# Adafruit_SEN5x_Adapter_Breakout.net
KiCad netlist of a schematic drawn in EAGLE
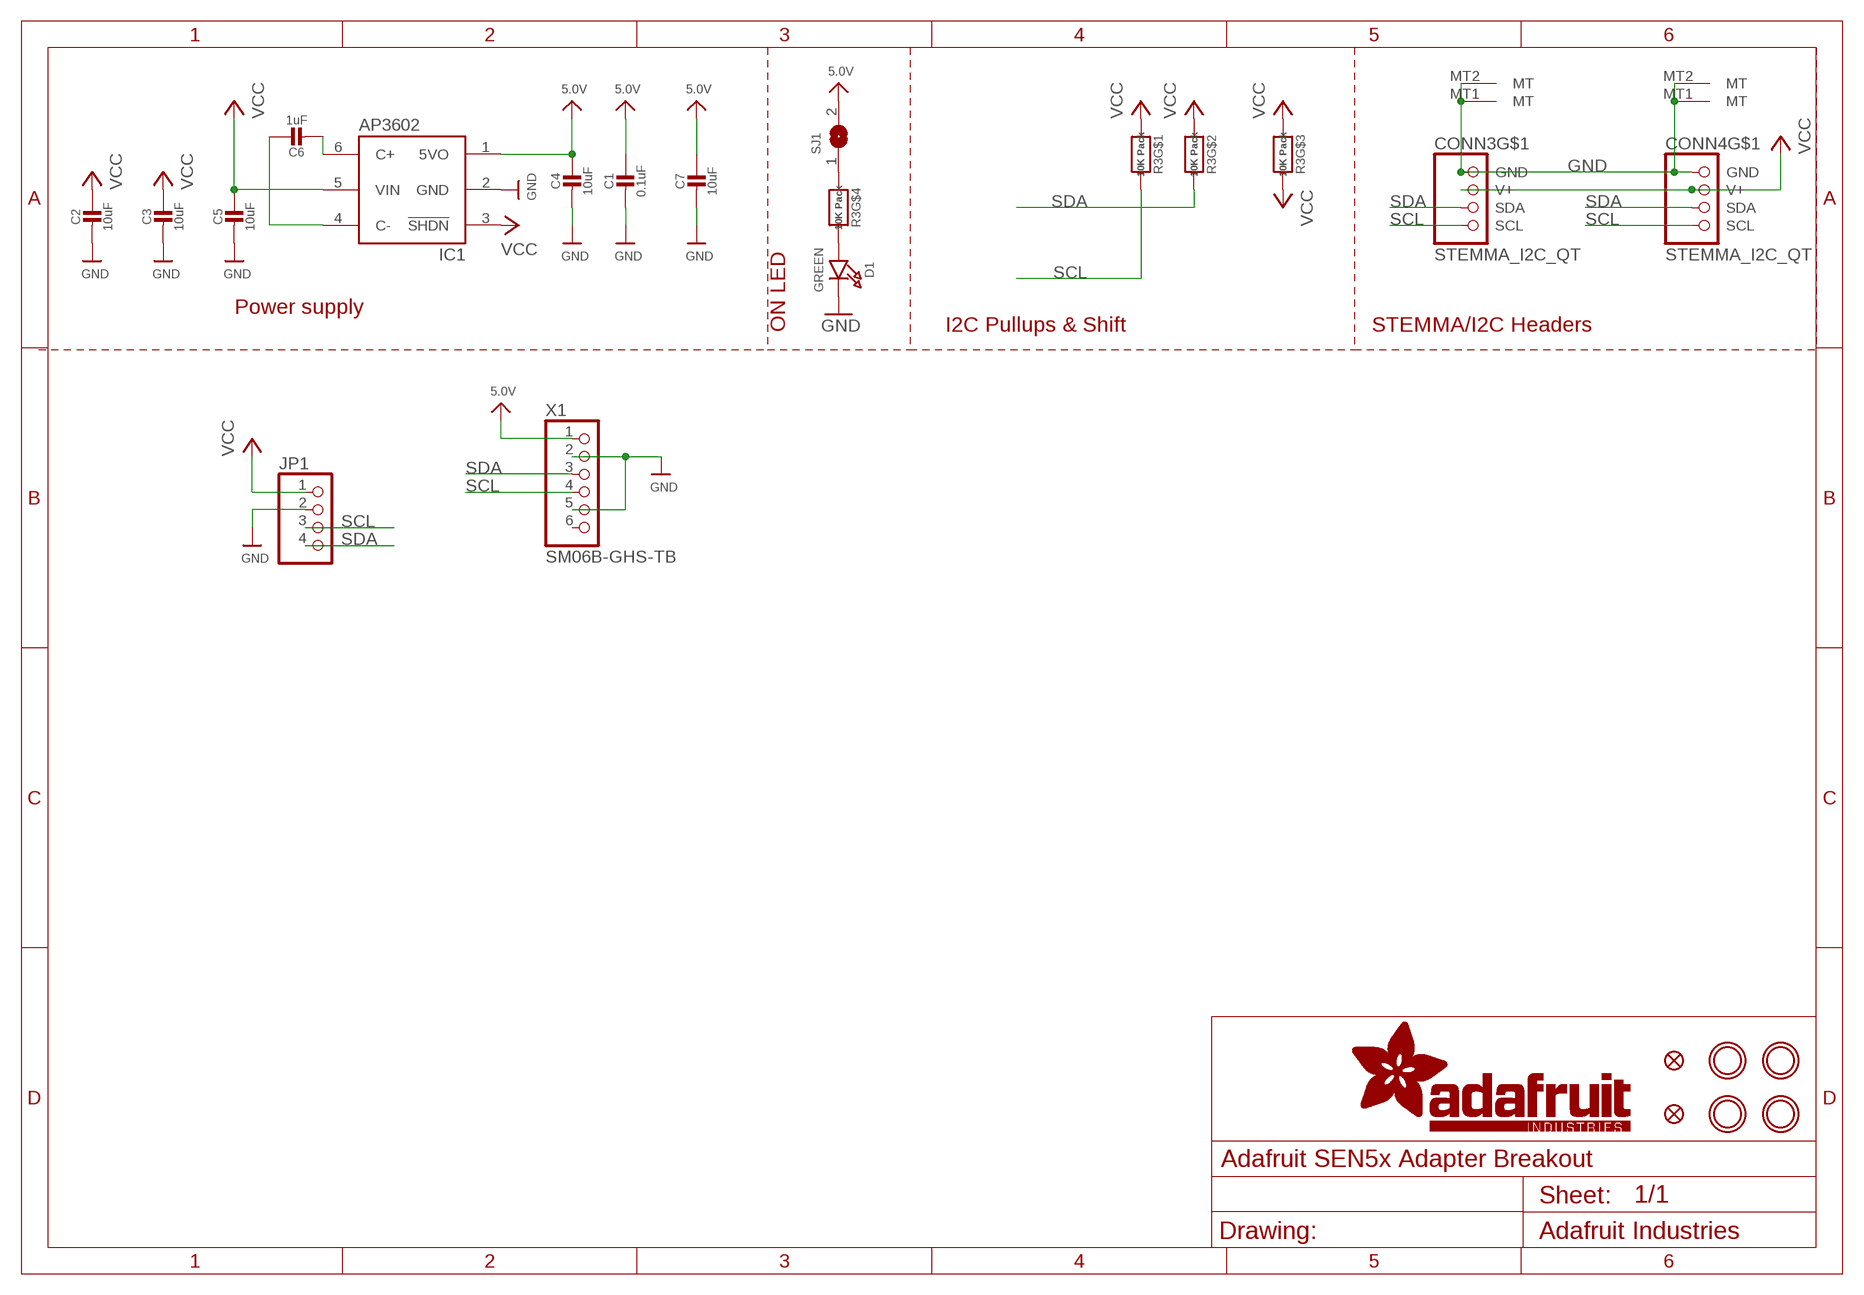
[diagram p0: schematic, sheet 1]

(export (version "E")
  (design (tool "Eeschema 10.0.6"))
  (components
    (comp (ref "C1")
      (value "0.1uF")
      (footprint "eagle-import:0603-NO")
      (libsource (lib "eagle-import") (part "CAP_CERAMIC0603_NO"))
    )
    (comp (ref "C2")
      (value "10uF")
      (footprint "eagle-import:0805-NO")
      (libsource (lib "eagle-import") (part "CAP_CERAMIC0805-NOOUTLINE"))
    )
    (comp (ref "C3")
      (value "10uF")
      (footprint "eagle-import:0805-NO")
      (libsource (lib "eagle-import") (part "CAP_CERAMIC0805-NOOUTLINE"))
    )
    (comp (ref "C4")
      (value "10uF")
      (footprint "eagle-import:0805-NO")
      (libsource (lib "eagle-import") (part "CAP_CERAMIC0805-NOOUTLINE"))
    )
    (comp (ref "C5")
      (value "10uF")
      (footprint "eagle-import:0805-NO")
      (libsource (lib "eagle-import") (part "CAP_CERAMIC0805-NOOUTLINE"))
    )
    (comp (ref "C6")
      (value "1uF")
      (footprint "eagle-import:0805-NO")
      (libsource (lib "eagle-import") (part "CAP_CERAMIC0805-NOOUTLINE"))
    )
    (comp (ref "C7")
      (value "10uF")
      (footprint "eagle-import:0805-NO")
      (libsource (lib "eagle-import") (part "CAP_CERAMIC0805-NOOUTLINE"))
    )
    (comp (ref "CONN3")
      (value "STEMMA_I2C_QT")
      (footprint "eagle-import:JST_SH4")
      (libsource (lib "eagle-import") (part "STEMMA_I2C_QT"))
    )
    (comp (ref "CONN4")
      (value "STEMMA_I2C_QT")
      (footprint "eagle-import:JST_SH4")
      (libsource (lib "eagle-import") (part "STEMMA_I2C_QT"))
    )
    (comp (ref "D1")
      (value "GREEN")
      (footprint "eagle-import:CHIPLED_0603_NOOUTLINE")
      (libsource (lib "eagle-import") (part "LED0603_NOOUTLINE"))
    )
    (comp (ref "FID3")
      (value "FIDUCIAL_1MM")
      (footprint "eagle-import:FIDUCIAL_1MM")
      (libsource (lib "eagle-import") (part "FIDUCIAL_1MM"))
    )
    (comp (ref "FID4")
      (value "FIDUCIAL_1MM")
      (footprint "eagle-import:FIDUCIAL_1MM")
      (libsource (lib "eagle-import") (part "FIDUCIAL_1MM"))
    )
    (comp (ref "IC1")
      (value "AP3602/RT9361")
      (footprint "eagle-import:SOT23-6")
      (libsource (lib "eagle-import") (part "AP3602"))
    )
    (comp (ref "JP1")
      (value "HEADER-1X4ROUND")
      (footprint "eagle-import:1X04_ROUND")
      (libsource (lib "eagle-import") (part "HEADER-1X4ROUND"))
    )
    (comp (ref "R3")
      (value "10K Pack")
      (footprint "eagle-import:RESPACK_4X0603")
      (libsource (lib "eagle-import") (part "RESISTOR_4PACK"))
    )
    (comp (ref "SJ1")
      (value "SOLDERJUMPERCLOSED")
      (footprint "eagle-import:SOLDERJUMPER_CLOSEDWIRE")
      (libsource (lib "eagle-import") (part "SOLDERJUMPERCLOSED"))
    )
    (comp (ref "U$1")
      (value "MOUNTINGHOLE2.5")
      (footprint "eagle-import:MOUNTINGHOLE_2.5_PLATED")
      (libsource (lib "eagle-import") (part "MOUNTINGHOLE2.5"))
    )
    (comp (ref "U$17")
      (value "MOUNTINGHOLE2.5")
      (footprint "eagle-import:MOUNTINGHOLE_2.5_PLATED")
      (libsource (lib "eagle-import") (part "MOUNTINGHOLE2.5"))
    )
    (comp (ref "U$19")
      (value "MOUNTINGHOLE2.5")
      (footprint "eagle-import:MOUNTINGHOLE_2.5_PLATED")
      (libsource (lib "eagle-import") (part "MOUNTINGHOLE2.5"))
    )
    (comp (ref "U$21")
      (value "MOUNTINGHOLE2.5")
      (footprint "eagle-import:MOUNTINGHOLE_2.5_PLATED")
      (libsource (lib "eagle-import") (part "MOUNTINGHOLE2.5"))
    )
    (comp (ref "X1")
      (value "SM06B-GHS-TB")
      (footprint "eagle-import:CONN_SM06B-GHS-TB_JST")
      (libsource (lib "eagle-import") (part "CON_JST_PH_6PIN_SM06S_GHS"))
    )
  )
  (nets
    (net (code "1") (name "/SCL") (class "Default")
      (node (ref "CONN3") (pin "4") (pinfunction "SCL_4") (pintype "passive"))
      (node (ref "CONN4") (pin "4") (pinfunction "SCL_4") (pintype "passive"))
      (node (ref "JP1") (pin "3") (pinfunction "3_3") (pintype "passive"))
      (node (ref "R3") (pin "8") (pinfunction "2_8") (pintype "passive"))
      (node (ref "X1") (pin "4") (pinfunction "4_4") (pintype "passive"))
    )
    (net (code "2") (name "/SDA") (class "Default")
      (node (ref "CONN3") (pin "3") (pinfunction "SDA_3") (pintype "passive"))
      (node (ref "CONN4") (pin "3") (pinfunction "SDA_3") (pintype "passive"))
      (node (ref "JP1") (pin "4") (pinfunction "4_4") (pintype "passive"))
      (node (ref "R3") (pin "7") (pinfunction "2_7") (pintype "passive"))
      (node (ref "X1") (pin "3") (pinfunction "3_3") (pintype "passive"))
    )
    (net (code "3") (name "5.0V") (class "Default")
      (node (ref "C1") (pin "1") (pinfunction "1_1") (pintype "passive"))
      (node (ref "C4") (pin "1") (pinfunction "1_1") (pintype "passive"))
      (node (ref "C7") (pin "1") (pinfunction "1_1") (pintype "passive"))
      (node (ref "IC1") (pin "1") (pinfunction "5VO_1") (pintype "power_in"))
      (node (ref "SJ1") (pin "2") (pinfunction "2_2") (pintype "passive"))
      (node (ref "X1") (pin "1") (pinfunction "1_1") (pintype "passive"))
    )
    (net (code "4") (name "GND") (class "Default")
      (node (ref "C1") (pin "2") (pinfunction "2_2") (pintype "passive"))
      (node (ref "C2") (pin "2") (pinfunction "2_2") (pintype "passive"))
      (node (ref "C3") (pin "2") (pinfunction "2_2") (pintype "passive"))
      (node (ref "C4") (pin "2") (pinfunction "2_2") (pintype "passive"))
      (node (ref "C5") (pin "2") (pinfunction "2_2") (pintype "passive"))
      (node (ref "C7") (pin "2") (pinfunction "2_2") (pintype "passive"))
      (node (ref "CONN3") (pin "1") (pinfunction "GND_1") (pintype "passive"))
      (node (ref "CONN3") (pin "MT1") (pinfunction "MT_MT1") (pintype "bidirectional"))
      (node (ref "CONN3") (pin "MT2") (pinfunction "MT_MT2") (pintype "bidirectional"))
      (node (ref "CONN4") (pin "1") (pinfunction "GND_1") (pintype "passive"))
      (node (ref "CONN4") (pin "MT1") (pinfunction "MT_MT1") (pintype "bidirectional"))
      (node (ref "CONN4") (pin "MT2") (pinfunction "MT_MT2") (pintype "bidirectional"))
      (node (ref "D1") (pin "C") (pinfunction "C_C") (pintype "passive"))
      (node (ref "IC1") (pin "2") (pinfunction "GND_2") (pintype "power_in"))
      (node (ref "JP1") (pin "2") (pinfunction "2_2") (pintype "passive"))
      (node (ref "X1") (pin "2") (pinfunction "2_2") (pintype "passive"))
      (node (ref "X1") (pin "5") (pinfunction "5_5") (pintype "passive"))
    )
    (net (code "5") (name "Net-(IC1-C+)") (class "Default")
      (node (ref "C6") (pin "2") (pinfunction "2_2") (pintype "passive"))
      (node (ref "IC1") (pin "6") (pinfunction "C+_6") (pintype "bidirectional"))
    )
    (net (code "6") (name "Net-(IC1-C-)") (class "Default")
      (node (ref "C6") (pin "1") (pinfunction "1_1") (pintype "passive"))
      (node (ref "IC1") (pin "4") (pinfunction "C-_4") (pintype "bidirectional"))
    )
    (net (code "7") (name "Net-(R3D-1)") (class "Default")
      (node (ref "R3") (pin "4") (pinfunction "1_4") (pintype "passive"))
      (node (ref "SJ1") (pin "1") (pinfunction "1_1") (pintype "passive"))
    )
    (net (code "8") (name "Net-(R3D-2)") (class "Default")
      (node (ref "D1") (pin "A") (pinfunction "A_A") (pintype "passive"))
      (node (ref "R3") (pin "5") (pinfunction "2_5") (pintype "passive"))
    )
    (net (code "9") (name "VCC") (class "Default")
      (node (ref "C2") (pin "1") (pinfunction "1_1") (pintype "passive"))
      (node (ref "C3") (pin "1") (pinfunction "1_1") (pintype "passive"))
      (node (ref "C5") (pin "1") (pinfunction "1_1") (pintype "passive"))
      (node (ref "CONN3") (pin "2") (pinfunction "V+_2") (pintype "passive"))
      (node (ref "CONN4") (pin "2") (pinfunction "V+_2") (pintype "passive"))
      (node (ref "IC1") (pin "3") (pinfunction "~{SHDN}_3") (pintype "input"))
      (node (ref "IC1") (pin "5") (pinfunction "VIN_5") (pintype "power_in"))
      (node (ref "JP1") (pin "1") (pinfunction "1_1") (pintype "passive"))
      (node (ref "R3") (pin "1") (pinfunction "1_1") (pintype "passive"))
      (node (ref "R3") (pin "2") (pinfunction "1_2") (pintype "passive"))
      (node (ref "R3") (pin "3") (pinfunction "1_3") (pintype "passive"))
      (node (ref "R3") (pin "6") (pinfunction "2_6") (pintype "passive"))
    )
    (net (code "10") (name "unconnected-(X1-Pad6)") (class "Default")
      (node (ref "X1") (pin "6") (pinfunction "6_6") (pintype "passive"))
    )
  )
)
